# mwscoretransponder2013_rteam.net
KiCad netlist of a schematic drawn in EAGLE
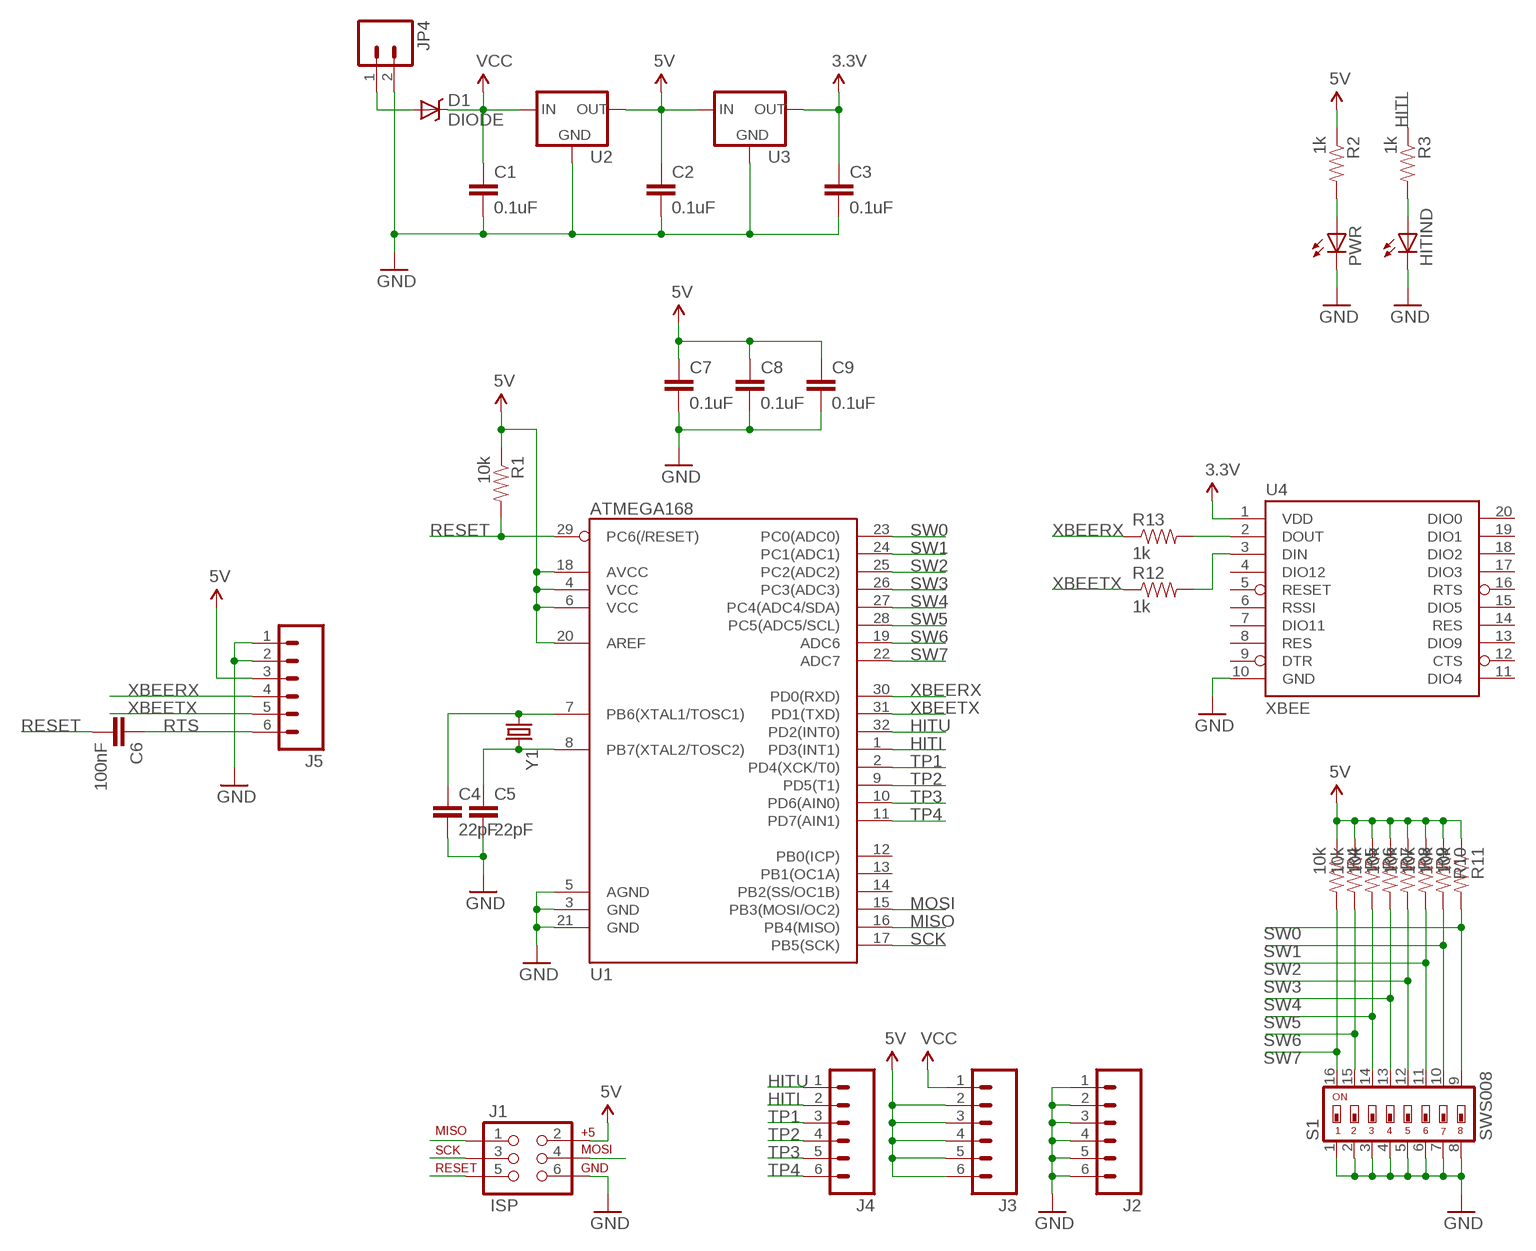
[diagram p0: schematic, sheet 1]

(export (version "E")
  (design (tool "Eeschema 10.0.6"))
  (components
    (comp (ref "C1")
      (value "0.1uF")
      (footprint "eagle-import:0603-CAP")
      (libsource (lib "eagle-import") (part "CAP0603-CAP"))
    )
    (comp (ref "C2")
      (value "0.1uF")
      (footprint "eagle-import:0603-CAP")
      (libsource (lib "eagle-import") (part "CAP0603-CAP"))
    )
    (comp (ref "C3")
      (value "0.1uF")
      (footprint "eagle-import:0603-CAP")
      (libsource (lib "eagle-import") (part "CAP0603-CAP"))
    )
    (comp (ref "C4")
      (value "22pF")
      (footprint "eagle-import:0603-CAP")
      (libsource (lib "eagle-import") (part "CAP0603-CAP"))
    )
    (comp (ref "C5")
      (value "22pF")
      (footprint "eagle-import:0603-CAP")
      (libsource (lib "eagle-import") (part "CAP0603-CAP"))
    )
    (comp (ref "C6")
      (value "100nF")
      (footprint "eagle-import:0603-CAP")
      (libsource (lib "eagle-import") (part "CAP0603-CAP"))
    )
    (comp (ref "C7")
      (value "0.1uF")
      (footprint "eagle-import:0603-CAP")
      (libsource (lib "eagle-import") (part "CAP0603-CAP"))
    )
    (comp (ref "C8")
      (value "0.1uF")
      (footprint "eagle-import:0603-CAP")
      (libsource (lib "eagle-import") (part "CAP0603-CAP"))
    )
    (comp (ref "C9")
      (value "0.1uF")
      (footprint "eagle-import:0603-CAP")
      (libsource (lib "eagle-import") (part "CAP0603-CAP"))
    )
    (comp (ref "D1")
      (value "DIODE")
      (footprint "eagle-import:SMA-DIODE")
      (libsource (lib "eagle-import") (part "DIODE-SCHOTTKY_"))
    )
    (comp (ref "HITIND")
      (value "LED0603")
      (footprint "eagle-import:LED-0603")
      (libsource (lib "eagle-import") (part "LED0603"))
    )
    (comp (ref "J1")
      (value "ISP")
      (footprint "eagle-import:2X3")
      (libsource (lib "eagle-import") (part "AVR_SPI_PRG_6PTH"))
    )
    (comp (ref "J2")
      (value "M06SIP")
      (footprint "eagle-import:1X06")
      (libsource (lib "eagle-import") (part "M06SIP"))
    )
    (comp (ref "J3")
      (value "M06SIP")
      (footprint "eagle-import:1X06")
      (libsource (lib "eagle-import") (part "M06SIP"))
    )
    (comp (ref "J4")
      (value "M06SIP")
      (footprint "eagle-import:1X06")
      (libsource (lib "eagle-import") (part "M06SIP"))
    )
    (comp (ref "J5")
      (value "M06SIP")
      (footprint "eagle-import:1X06")
      (libsource (lib "eagle-import") (part "M06SIP"))
    )
    (comp (ref "JP4")
      (value "M023.5MM_LOCK")
      (footprint "eagle-import:SCREWTERMINAL-3.5MM-2_LOCK")
      (libsource (lib "eagle-import") (part "M023.5MM_LOCK"))
    )
    (comp (ref "PWR")
      (value "LED0603")
      (footprint "eagle-import:LED-0603")
      (libsource (lib "eagle-import") (part "LED0603"))
    )
    (comp (ref "R1")
      (value "10k")
      (footprint "eagle-import:0603-RES")
      (libsource (lib "eagle-import") (part "RESISTOR0603-RES"))
    )
    (comp (ref "R2")
      (value "1k")
      (footprint "eagle-import:0603-RES")
      (libsource (lib "eagle-import") (part "RESISTOR0603-RES"))
    )
    (comp (ref "R3")
      (value "1k")
      (footprint "eagle-import:0603-RES")
      (libsource (lib "eagle-import") (part "RESISTOR0603-RES"))
    )
    (comp (ref "R4")
      (value "10k")
      (footprint "eagle-import:0603-RES")
      (libsource (lib "eagle-import") (part "RESISTOR0603-RES"))
    )
    (comp (ref "R5")
      (value "10k")
      (footprint "eagle-import:0603-RES")
      (libsource (lib "eagle-import") (part "RESISTOR0603-RES"))
    )
    (comp (ref "R6")
      (value "10k")
      (footprint "eagle-import:0603-RES")
      (libsource (lib "eagle-import") (part "RESISTOR0603-RES"))
    )
    (comp (ref "R7")
      (value "10k")
      (footprint "eagle-import:0603-RES")
      (libsource (lib "eagle-import") (part "RESISTOR0603-RES"))
    )
    (comp (ref "R8")
      (value "10k")
      (footprint "eagle-import:0603-RES")
      (libsource (lib "eagle-import") (part "RESISTOR0603-RES"))
    )
    (comp (ref "R9")
      (value "10k")
      (footprint "eagle-import:0603-RES")
      (libsource (lib "eagle-import") (part "RESISTOR0603-RES"))
    )
    (comp (ref "R10")
      (value "10k")
      (footprint "eagle-import:0603-RES")
      (libsource (lib "eagle-import") (part "RESISTOR0603-RES"))
    )
    (comp (ref "R11")
      (value "10k")
      (footprint "eagle-import:0603-RES")
      (libsource (lib "eagle-import") (part "RESISTOR0603-RES"))
    )
    (comp (ref "R12")
      (value "1k")
      (footprint "eagle-import:0603-RES")
      (libsource (lib "eagle-import") (part "RESISTOR0603-RES"))
    )
    (comp (ref "R13")
      (value "1k")
      (footprint "eagle-import:0603-RES")
      (libsource (lib "eagle-import") (part "RESISTOR0603-RES"))
    )
    (comp (ref "S1")
      (value "SWS008")
      (footprint "eagle-import:SMS-008")
      (libsource (lib "eagle-import") (part "SWS008"))
    )
    (comp (ref "U1")
      (value "ATMEGA168")
      (footprint "eagle-import:TQFP32-08")
      (libsource (lib "eagle-import") (part "ATMEGA168"))
    )
    (comp (ref "U2")
      (value "V_REG_MIC2920")
      (footprint "eagle-import:SOT223")
      (libsource (lib "eagle-import") (part "V_REG_MIC2920"))
    )
    (comp (ref "U3")
      (value "V_REG_MIC2920")
      (footprint "eagle-import:SOT223")
      (libsource (lib "eagle-import") (part "V_REG_MIC2920"))
    )
    (comp (ref "U4")
      (value "XBEE")
      (footprint "eagle-import:XBEE-SMD")
      (libsource (lib "eagle-import") (part "XBEE-1B3"))
    )
    (comp (ref "Y1")
      (value "CRYSTAL5X3")
      (footprint "eagle-import:CRYSTAL-SMD-5X3")
      (libsource (lib "eagle-import") (part "CRYSTAL5X3"))
    )
  )
  (nets
    (net (code "1") (name "/HITI") (class "Default")
      (node (ref "J4") (pin "2") (pinfunction "2_2") (pintype "passive"))
      (node (ref "R3") (pin "1") (pinfunction "1_1") (pintype "passive"))
      (node (ref "U1") (pin "1") (pinfunction "PD3(INT1)_1") (pintype "bidirectional"))
    )
    (net (code "2") (name "/HITU") (class "Default")
      (node (ref "J4") (pin "1") (pinfunction "1_1") (pintype "passive"))
      (node (ref "U1") (pin "32") (pinfunction "PD2(INT0)_32") (pintype "bidirectional"))
    )
    (net (code "3") (name "/MISO") (class "Default")
      (node (ref "J1") (pin "1") (pinfunction "1_1") (pintype "passive"))
      (node (ref "U1") (pin "16") (pinfunction "PB4(MISO)_16") (pintype "bidirectional"))
    )
    (net (code "4") (name "/MOSI") (class "Default")
      (node (ref "J1") (pin "4") (pinfunction "4_4") (pintype "passive"))
      (node (ref "U1") (pin "15") (pinfunction "PB3(MOSI/OC2)_15") (pintype "bidirectional"))
    )
    (net (code "5") (name "/RESET") (class "Default")
      (node (ref "C6") (pin "2") (pinfunction "2_2") (pintype "passive"))
      (node (ref "J1") (pin "5") (pinfunction "5_5") (pintype "passive"))
      (node (ref "R1") (pin "2") (pinfunction "2_2") (pintype "passive"))
      (node (ref "U1") (pin "29") (pinfunction "PC6(/RESET)_29") (pintype "bidirectional"))
    )
    (net (code "6") (name "/RTS") (class "Default")
      (node (ref "C6") (pin "1") (pinfunction "1_1") (pintype "passive"))
      (node (ref "J5") (pin "6") (pinfunction "6_6") (pintype "passive"))
    )
    (net (code "7") (name "/SCK") (class "Default")
      (node (ref "J1") (pin "3") (pinfunction "3_3") (pintype "passive"))
      (node (ref "U1") (pin "17") (pinfunction "PB5(SCK)_17") (pintype "bidirectional"))
    )
    (net (code "8") (name "/SW0") (class "Default")
      (node (ref "R11") (pin "2") (pinfunction "2_2") (pintype "passive"))
      (node (ref "S1") (pin "9") (pinfunction "9_9") (pintype "passive"))
      (node (ref "U1") (pin "23") (pinfunction "PC0(ADC0)_23") (pintype "bidirectional"))
    )
    (net (code "9") (name "/SW1") (class "Default")
      (node (ref "R10") (pin "2") (pinfunction "2_2") (pintype "passive"))
      (node (ref "S1") (pin "10") (pinfunction "10_10") (pintype "passive"))
      (node (ref "U1") (pin "24") (pinfunction "PC1(ADC1)_24") (pintype "bidirectional"))
    )
    (net (code "10") (name "/SW2") (class "Default")
      (node (ref "R9") (pin "2") (pinfunction "2_2") (pintype "passive"))
      (node (ref "S1") (pin "11") (pinfunction "11_11") (pintype "passive"))
      (node (ref "U1") (pin "25") (pinfunction "PC2(ADC2)_25") (pintype "bidirectional"))
    )
    (net (code "11") (name "/SW3") (class "Default")
      (node (ref "R8") (pin "2") (pinfunction "2_2") (pintype "passive"))
      (node (ref "S1") (pin "12") (pinfunction "12_12") (pintype "passive"))
      (node (ref "U1") (pin "26") (pinfunction "PC3(ADC3)_26") (pintype "bidirectional"))
    )
    (net (code "12") (name "/SW4") (class "Default")
      (node (ref "R7") (pin "2") (pinfunction "2_2") (pintype "passive"))
      (node (ref "S1") (pin "13") (pinfunction "13_13") (pintype "passive"))
      (node (ref "U1") (pin "27") (pinfunction "PC4(ADC4/SDA)_27") (pintype "bidirectional"))
    )
    (net (code "13") (name "/SW5") (class "Default")
      (node (ref "R6") (pin "2") (pinfunction "2_2") (pintype "passive"))
      (node (ref "S1") (pin "14") (pinfunction "14_14") (pintype "passive"))
      (node (ref "U1") (pin "28") (pinfunction "PC5(ADC5/SCL)_28") (pintype "bidirectional"))
    )
    (net (code "14") (name "/SW6") (class "Default")
      (node (ref "R5") (pin "2") (pinfunction "2_2") (pintype "passive"))
      (node (ref "S1") (pin "15") (pinfunction "15_15") (pintype "passive"))
      (node (ref "U1") (pin "19") (pinfunction "ADC6_19") (pintype "bidirectional"))
    )
    (net (code "15") (name "/SW7") (class "Default")
      (node (ref "R4") (pin "2") (pinfunction "2_2") (pintype "passive"))
      (node (ref "S1") (pin "16") (pinfunction "16_16") (pintype "passive"))
      (node (ref "U1") (pin "22") (pinfunction "ADC7_22") (pintype "bidirectional"))
    )
    (net (code "16") (name "/TP1") (class "Default")
      (node (ref "J4") (pin "3") (pinfunction "3_3") (pintype "passive"))
      (node (ref "U1") (pin "2") (pinfunction "PD4(XCK/T0)_2") (pintype "bidirectional"))
    )
    (net (code "17") (name "/TP2") (class "Default")
      (node (ref "J4") (pin "4") (pinfunction "4_4") (pintype "passive"))
      (node (ref "U1") (pin "9") (pinfunction "PD5(T1)_9") (pintype "bidirectional"))
    )
    (net (code "18") (name "/TP3") (class "Default")
      (node (ref "J4") (pin "5") (pinfunction "5_5") (pintype "passive"))
      (node (ref "U1") (pin "10") (pinfunction "PD6(AIN0)_10") (pintype "bidirectional"))
    )
    (net (code "19") (name "/TP4") (class "Default")
      (node (ref "J4") (pin "6") (pinfunction "6_6") (pintype "passive"))
      (node (ref "U1") (pin "11") (pinfunction "PD7(AIN1)_11") (pintype "bidirectional"))
    )
    (net (code "20") (name "/XBEERX") (class "Default")
      (node (ref "J5") (pin "4") (pinfunction "4_4") (pintype "passive"))
      (node (ref "R13") (pin "1") (pinfunction "1_1") (pintype "passive"))
      (node (ref "U1") (pin "30") (pinfunction "PD0(RXD)_30") (pintype "bidirectional"))
    )
    (net (code "21") (name "/XBEETX") (class "Default")
      (node (ref "J5") (pin "5") (pinfunction "5_5") (pintype "passive"))
      (node (ref "R12") (pin "1") (pinfunction "1_1") (pintype "passive"))
      (node (ref "U1") (pin "31") (pinfunction "PD1(TXD)_31") (pintype "bidirectional"))
    )
    (net (code "22") (name "3.3V") (class "Default")
      (node (ref "C3") (pin "1") (pinfunction "1_1") (pintype "passive"))
      (node (ref "U3") (pin "3") (pinfunction "OUT_3") (pintype "output"))
      (node (ref "U4") (pin "1") (pinfunction "VDD_1") (pintype "power_in"))
    )
    (net (code "23") (name "5V") (class "Default")
      (node (ref "C2") (pin "1") (pinfunction "1_1") (pintype "passive"))
      (node (ref "C7") (pin "1") (pinfunction "1_1") (pintype "passive"))
      (node (ref "C8") (pin "1") (pinfunction "1_1") (pintype "passive"))
      (node (ref "C9") (pin "1") (pinfunction "1_1") (pintype "passive"))
      (node (ref "J1") (pin "2") (pinfunction "2_2") (pintype "passive"))
      (node (ref "J3") (pin "2") (pinfunction "2_2") (pintype "passive"))
      (node (ref "J3") (pin "3") (pinfunction "3_3") (pintype "passive"))
      (node (ref "J3") (pin "4") (pinfunction "4_4") (pintype "passive"))
      (node (ref "J3") (pin "5") (pinfunction "5_5") (pintype "passive"))
      (node (ref "J3") (pin "6") (pinfunction "6_6") (pintype "passive"))
      (node (ref "J5") (pin "3") (pinfunction "3_3") (pintype "passive"))
      (node (ref "R1") (pin "1") (pinfunction "1_1") (pintype "passive"))
      (node (ref "R10") (pin "1") (pinfunction "1_1") (pintype "passive"))
      (node (ref "R11") (pin "1") (pinfunction "1_1") (pintype "passive"))
      (node (ref "R2") (pin "1") (pinfunction "1_1") (pintype "passive"))
      (node (ref "R4") (pin "1") (pinfunction "1_1") (pintype "passive"))
      (node (ref "R5") (pin "1") (pinfunction "1_1") (pintype "passive"))
      (node (ref "R6") (pin "1") (pinfunction "1_1") (pintype "passive"))
      (node (ref "R7") (pin "1") (pinfunction "1_1") (pintype "passive"))
      (node (ref "R8") (pin "1") (pinfunction "1_1") (pintype "passive"))
      (node (ref "R9") (pin "1") (pinfunction "1_1") (pintype "passive"))
      (node (ref "U1") (pin "18") (pinfunction "AVCC_18") (pintype "bidirectional"))
      (node (ref "U1") (pin "20") (pinfunction "AREF_20") (pintype "bidirectional"))
      (node (ref "U1") (pin "4") (pinfunction "VCC_4") (pintype "bidirectional"))
      (node (ref "U1") (pin "6") (pinfunction "VCC_6") (pintype "bidirectional"))
      (node (ref "U2") (pin "3") (pinfunction "OUT_3") (pintype "output"))
      (node (ref "U3") (pin "1") (pinfunction "IN_1") (pintype "input"))
    )
    (net (code "24") (name "GND") (class "Default")
      (node (ref "C1") (pin "2") (pinfunction "2_2") (pintype "passive"))
      (node (ref "C2") (pin "2") (pinfunction "2_2") (pintype "passive"))
      (node (ref "C3") (pin "2") (pinfunction "2_2") (pintype "passive"))
      (node (ref "C4") (pin "2") (pinfunction "2_2") (pintype "passive"))
      (node (ref "C5") (pin "2") (pinfunction "2_2") (pintype "passive"))
      (node (ref "C7") (pin "2") (pinfunction "2_2") (pintype "passive"))
      (node (ref "C8") (pin "2") (pinfunction "2_2") (pintype "passive"))
      (node (ref "C9") (pin "2") (pinfunction "2_2") (pintype "passive"))
      (node (ref "HITIND") (pin "C") (pinfunction "C_C") (pintype "passive"))
      (node (ref "J1") (pin "6") (pinfunction "6_6") (pintype "passive"))
      (node (ref "J2") (pin "1") (pinfunction "1_1") (pintype "passive"))
      (node (ref "J2") (pin "2") (pinfunction "2_2") (pintype "passive"))
      (node (ref "J2") (pin "3") (pinfunction "3_3") (pintype "passive"))
      (node (ref "J2") (pin "4") (pinfunction "4_4") (pintype "passive"))
      (node (ref "J2") (pin "5") (pinfunction "5_5") (pintype "passive"))
      (node (ref "J2") (pin "6") (pinfunction "6_6") (pintype "passive"))
      (node (ref "J5") (pin "1") (pinfunction "1_1") (pintype "passive"))
      (node (ref "J5") (pin "2") (pinfunction "2_2") (pintype "passive"))
      (node (ref "JP4") (pin "2") (pinfunction "2_2") (pintype "passive"))
      (node (ref "PWR") (pin "C") (pinfunction "C_C") (pintype "passive"))
      (node (ref "S1") (pin "1") (pinfunction "1_1") (pintype "passive"))
      (node (ref "S1") (pin "2") (pinfunction "2_2") (pintype "passive"))
      (node (ref "S1") (pin "3") (pinfunction "3_3") (pintype "passive"))
      (node (ref "S1") (pin "4") (pinfunction "4_4") (pintype "passive"))
      (node (ref "S1") (pin "5") (pinfunction "5_5") (pintype "passive"))
      (node (ref "S1") (pin "6") (pinfunction "6_6") (pintype "passive"))
      (node (ref "S1") (pin "7") (pinfunction "7_7") (pintype "passive"))
      (node (ref "S1") (pin "8") (pinfunction "8_8") (pintype "passive"))
      (node (ref "U1") (pin "21") (pinfunction "GND_21") (pintype "bidirectional"))
      (node (ref "U1") (pin "3") (pinfunction "GND_3") (pintype "bidirectional"))
      (node (ref "U1") (pin "5") (pinfunction "AGND_5") (pintype "bidirectional"))
      (node (ref "U2") (pin "2") (pinfunction "GND_2") (pintype "input"))
      (node (ref "U3") (pin "2") (pinfunction "GND_2") (pintype "input"))
      (node (ref "U4") (pin "10") (pinfunction "GND_10") (pintype "power_in"))
    )
    (net (code "25") (name "Net-(D1-PadA)") (class "Default")
      (node (ref "D1") (pin "A") (pinfunction "A_A") (pintype "passive"))
      (node (ref "JP4") (pin "1") (pinfunction "1_1") (pintype "passive"))
    )
    (net (code "26") (name "Net-(HITIND-PadA)") (class "Default")
      (node (ref "HITIND") (pin "A") (pinfunction "A_A") (pintype "passive"))
      (node (ref "R3") (pin "2") (pinfunction "2_2") (pintype "passive"))
    )
    (net (code "27") (name "Net-(PWR-PadA)") (class "Default")
      (node (ref "PWR") (pin "A") (pinfunction "A_A") (pintype "passive"))
      (node (ref "R2") (pin "2") (pinfunction "2_2") (pintype "passive"))
    )
    (net (code "28") (name "Net-(U1-PB6(XTAL1{slash}TOSC1))") (class "Default")
      (node (ref "C4") (pin "1") (pinfunction "1_1") (pintype "passive"))
      (node (ref "U1") (pin "7") (pinfunction "PB6(XTAL1/TOSC1)_7") (pintype "bidirectional"))
      (node (ref "Y1") (pin "1") (pinfunction "1_1") (pintype "passive"))
    )
    (net (code "29") (name "Net-(U1-PB7(XTAL2{slash}TOSC2))") (class "Default")
      (node (ref "C5") (pin "1") (pinfunction "1_1") (pintype "passive"))
      (node (ref "U1") (pin "8") (pinfunction "PB7(XTAL2/TOSC2)_8") (pintype "bidirectional"))
      (node (ref "Y1") (pin "3") (pinfunction "2_3") (pintype "passive"))
    )
    (net (code "30") (name "Net-(U4-DIN)") (class "Default")
      (node (ref "R12") (pin "2") (pinfunction "2_2") (pintype "passive"))
      (node (ref "U4") (pin "3") (pinfunction "DIN_3") (pintype "input"))
    )
    (net (code "31") (name "Net-(U4-DOUT)") (class "Default")
      (node (ref "R13") (pin "2") (pinfunction "2_2") (pintype "passive"))
      (node (ref "U4") (pin "2") (pinfunction "DOUT_2") (pintype "output"))
    )
    (net (code "32") (name "VCC") (class "Default")
      (node (ref "C1") (pin "1") (pinfunction "1_1") (pintype "passive"))
      (node (ref "D1") (pin "C") (pinfunction "C_C") (pintype "passive"))
      (node (ref "J3") (pin "1") (pinfunction "1_1") (pintype "passive"))
      (node (ref "U2") (pin "1") (pinfunction "IN_1") (pintype "input"))
    )
    (net (code "33") (name "unconnected-(U1-PB0(ICP)-Pad12)") (class "Default")
      (node (ref "U1") (pin "12") (pinfunction "PB0(ICP)_12") (pintype "bidirectional"))
    )
    (net (code "34") (name "unconnected-(U1-PB1(OC1A)-Pad13)") (class "Default")
      (node (ref "U1") (pin "13") (pinfunction "PB1(OC1A)_13") (pintype "bidirectional"))
    )
    (net (code "35") (name "unconnected-(U1-PB2(SS{slash}OC1B)-Pad14)") (class "Default")
      (node (ref "U1") (pin "14") (pinfunction "PB2(SS/OC1B)_14") (pintype "bidirectional"))
    )
    (net (code "36") (name "unconnected-(U4-CTS-Pad12)") (class "Default")
      (node (ref "U4") (pin "12") (pinfunction "CTS_12") (pintype "output"))
    )
    (net (code "37") (name "unconnected-(U4-DIO0-Pad20)") (class "Default")
      (node (ref "U4") (pin "20") (pinfunction "DIO0_20") (pintype "bidirectional"))
    )
    (net (code "38") (name "unconnected-(U4-DIO1-Pad19)") (class "Default")
      (node (ref "U4") (pin "19") (pinfunction "DIO1_19") (pintype "bidirectional"))
    )
    (net (code "39") (name "unconnected-(U4-DIO2-Pad18)") (class "Default")
      (node (ref "U4") (pin "18") (pinfunction "DIO2_18") (pintype "bidirectional"))
    )
    (net (code "40") (name "unconnected-(U4-DIO3-Pad17)") (class "Default")
      (node (ref "U4") (pin "17") (pinfunction "DIO3_17") (pintype "bidirectional"))
    )
    (net (code "41") (name "unconnected-(U4-DIO4-Pad11)") (class "Default")
      (node (ref "U4") (pin "11") (pinfunction "DIO4_11") (pintype "bidirectional"))
    )
    (net (code "42") (name "unconnected-(U4-DIO5-Pad15)") (class "Default")
      (node (ref "U4") (pin "15") (pinfunction "DIO5_15") (pintype "bidirectional"))
    )
    (net (code "43") (name "unconnected-(U4-DIO9-Pad13)") (class "Default")
      (node (ref "U4") (pin "13") (pinfunction "DIO9_13") (pintype "bidirectional"))
    )
    (net (code "44") (name "unconnected-(U4-DIO11-Pad7)") (class "Default")
      (node (ref "U4") (pin "7") (pinfunction "DIO11_7") (pintype "bidirectional"))
    )
    (net (code "45") (name "unconnected-(U4-DIO12-Pad4)") (class "Default")
      (node (ref "U4") (pin "4") (pinfunction "DIO12_4") (pintype "bidirectional"))
    )
    (net (code "46") (name "unconnected-(U4-DTR-Pad9)") (class "Default")
      (node (ref "U4") (pin "9") (pinfunction "DTR_9") (pintype "bidirectional"))
    )
    (net (code "47") (name "unconnected-(U4-RES-Pad8)") (class "Default")
      (node (ref "U4") (pin "8") (pinfunction "RES_8") (pintype "bidirectional"))
    )
    (net (code "48") (name "unconnected-(U4-RES-Pad14)") (class "Default")
      (node (ref "U4") (pin "14") (pinfunction "RES_14") (pintype "bidirectional"))
    )
    (net (code "49") (name "unconnected-(U4-RESET-Pad5)") (class "Default")
      (node (ref "U4") (pin "5") (pinfunction "RESET_5") (pintype "input"))
    )
    (net (code "50") (name "unconnected-(U4-RSSI-Pad6)") (class "Default")
      (node (ref "U4") (pin "6") (pinfunction "RSSI_6") (pintype "bidirectional"))
    )
    (net (code "51") (name "unconnected-(U4-RTS-Pad16)") (class "Default")
      (node (ref "U4") (pin "16") (pinfunction "RTS_16") (pintype "input"))
    )
  )
)
